# LM3S811_Module.net
KiCad netlist of a schematic drawn in EAGLE
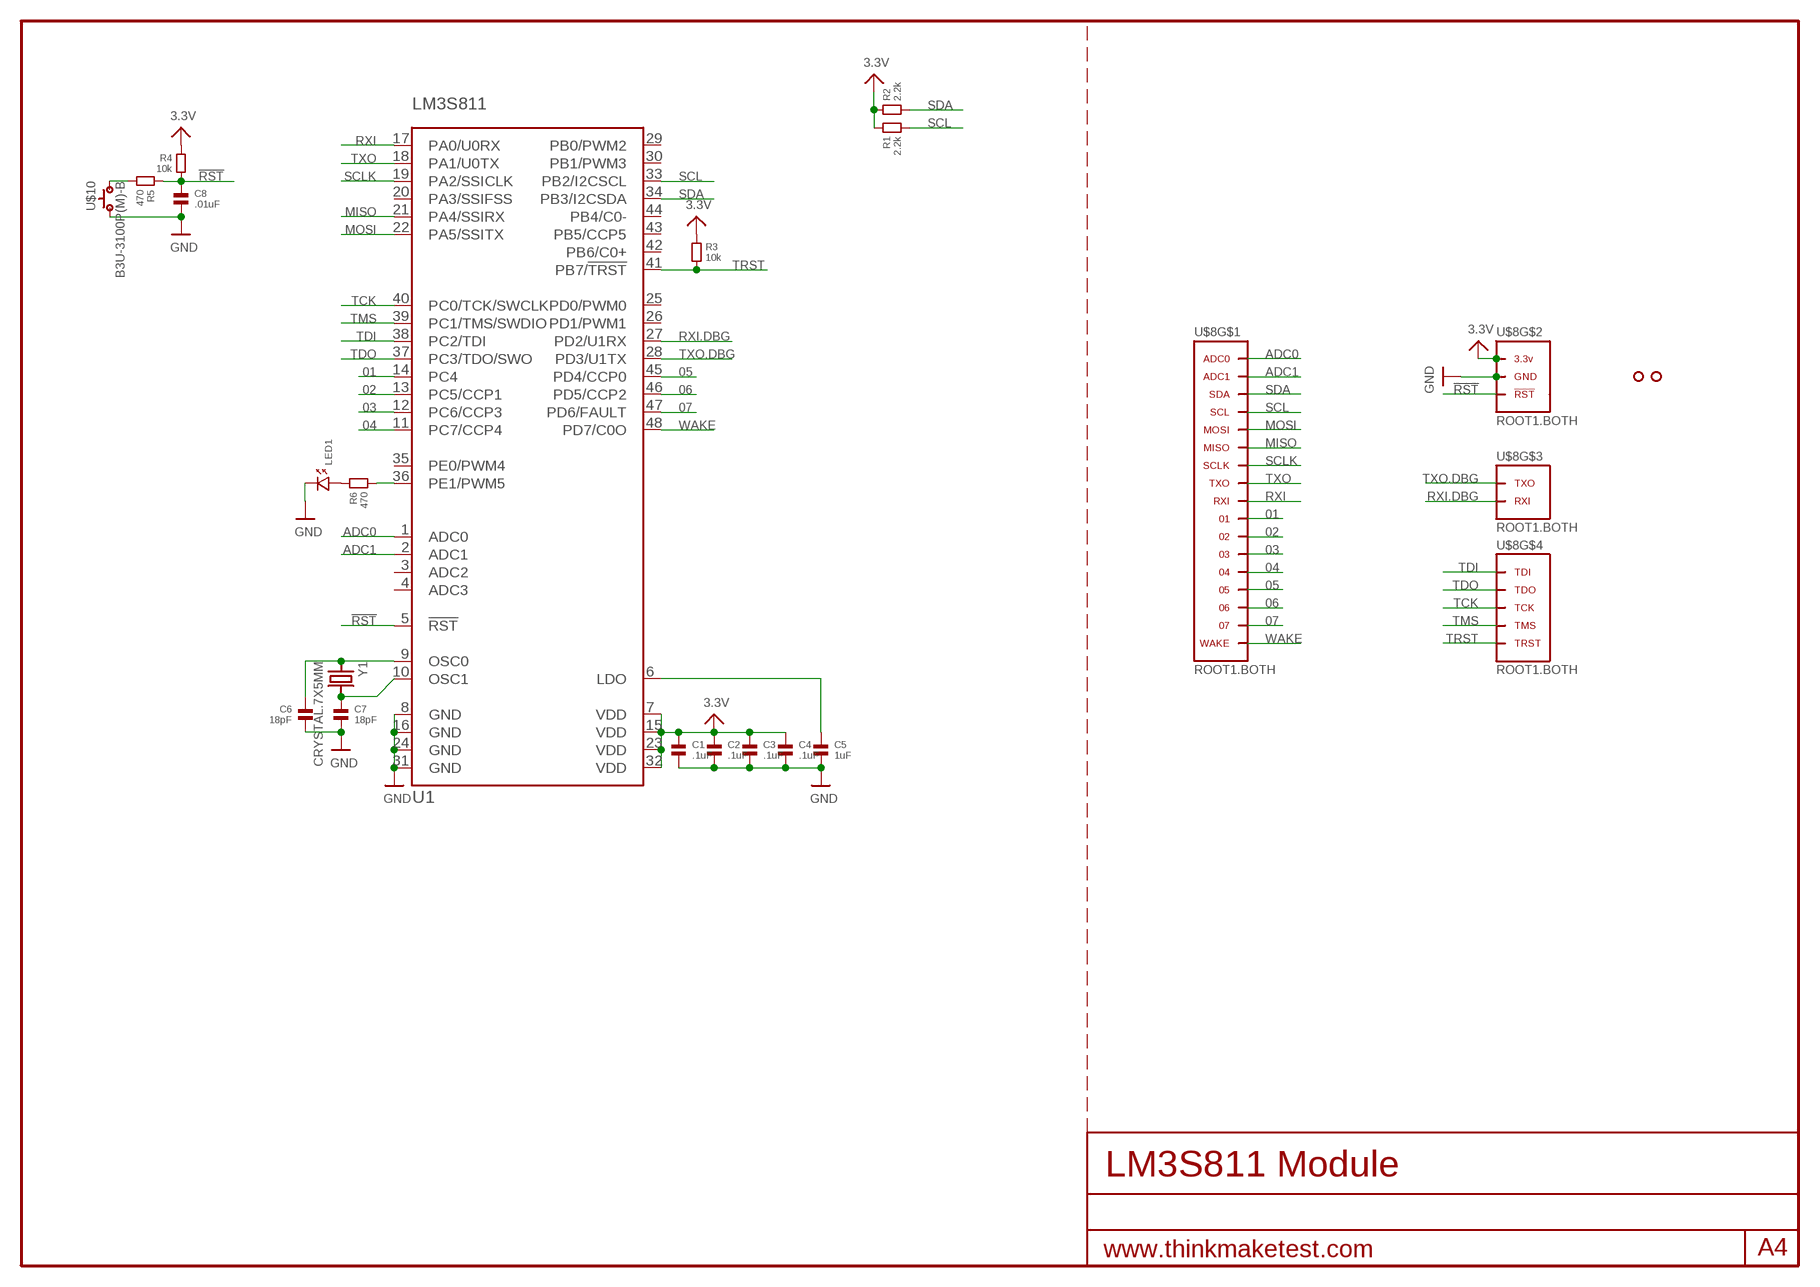
[diagram p0: schematic, sheet 1]

(export (version "E")
  (design (tool "Eeschema 10.0.6"))
  (components
    (comp (ref "C1")
      (value ".1uF")
      (footprint "eagle-import:0603")
      (libsource (lib "eagle-import") (part "CAPACITOR.0603"))
    )
    (comp (ref "C2")
      (value ".1uF")
      (footprint "eagle-import:0603")
      (libsource (lib "eagle-import") (part "CAPACITOR.0603"))
    )
    (comp (ref "C3")
      (value ".1uF")
      (footprint "eagle-import:0603")
      (libsource (lib "eagle-import") (part "CAPACITOR.0603"))
    )
    (comp (ref "C4")
      (value ".1uF")
      (footprint "eagle-import:0603")
      (libsource (lib "eagle-import") (part "CAPACITOR.0603"))
    )
    (comp (ref "C5")
      (value "1uF")
      (footprint "eagle-import:0603")
      (libsource (lib "eagle-import") (part "CAPACITOR.0603"))
    )
    (comp (ref "C6")
      (value "18pF")
      (footprint "eagle-import:0603")
      (libsource (lib "eagle-import") (part "CAPACITOR.0603"))
    )
    (comp (ref "C7")
      (value "18pF")
      (footprint "eagle-import:0603")
      (libsource (lib "eagle-import") (part "CAPACITOR.0603"))
    )
    (comp (ref "C8")
      (value ".01uF")
      (footprint "eagle-import:0603")
      (libsource (lib "eagle-import") (part "CAPACITOR.0603"))
    )
    (comp (ref "LED1")
      (value "LED.0603")
      (footprint "eagle-import:0603.LED")
      (libsource (lib "eagle-import") (part "LED.0603"))
    )
    (comp (ref "R1")
      (value "2.2k")
      (footprint "eagle-import:0603")
      (libsource (lib "eagle-import") (part "RESISTOR.0603"))
    )
    (comp (ref "R2")
      (value "2.2k")
      (footprint "eagle-import:0603")
      (libsource (lib "eagle-import") (part "RESISTOR.0603"))
    )
    (comp (ref "R3")
      (value "10k")
      (footprint "eagle-import:0603")
      (libsource (lib "eagle-import") (part "RESISTOR.0603"))
    )
    (comp (ref "R4")
      (value "10k")
      (footprint "eagle-import:0603")
      (libsource (lib "eagle-import") (part "RESISTOR.0603"))
    )
    (comp (ref "R5")
      (value "470")
      (footprint "eagle-import:0603")
      (libsource (lib "eagle-import") (part "RESISTOR.0603"))
    )
    (comp (ref "R6")
      (value "470")
      (footprint "eagle-import:0603")
      (libsource (lib "eagle-import") (part "RESISTOR.0603"))
    )
    (comp (ref "U$3")
      (value "HOLE.2MM")
      (footprint "eagle-import:2MM")
      (libsource (lib "eagle-import") (part "HOLE.2MM"))
    )
    (comp (ref "U$4")
      (value "HOLE.2MM")
      (footprint "eagle-import:2MM")
      (libsource (lib "eagle-import") (part "HOLE.2MM"))
    )
    (comp (ref "U$8")
      (value "ROOT1.BOTH")
      (footprint "eagle-import:ROOT1.BOTH")
      (libsource (lib "eagle-import") (part "ROOT1.BOTH"))
    )
    (comp (ref "U$10")
      (value "B3U-3100P(M)-B")
      (footprint "eagle-import:B3U-3100P(M)-B")
      (libsource (lib "eagle-import") (part "B3U-3100P(M)-B"))
    )
    (comp (ref "U1")
      (value "LM3S811")
      (footprint "eagle-import:QFP50P900X900X160-48N")
      (libsource (lib "eagle-import") (part "LM3S811"))
    )
    (comp (ref "Y1")
      (value "CRYSTAL.7X5MM")
      (footprint "eagle-import:7X5MM")
      (libsource (lib "eagle-import") (part "CRYSTAL.7X5MM"))
    )
  )
  (nets
    (net (code "1") (name "/01") (class "Default")
      (node (ref "U$8") (pin "01") (pinfunction "01_01") (pintype "bidirectional"))
      (node (ref "U$8") (pin "01@1") (pinfunction "01_01@1") (pintype "bidirectional"))
      (node (ref "U$8") (pin "01@VIA") (pinfunction "01_01@VIA") (pintype "bidirectional"))
      (node (ref "U1") (pin "14") (pinfunction "PC4_14") (pintype "bidirectional"))
    )
    (net (code "2") (name "/02") (class "Default")
      (node (ref "U$8") (pin "02") (pinfunction "02_02") (pintype "bidirectional"))
      (node (ref "U$8") (pin "02@1") (pinfunction "02_02@1") (pintype "bidirectional"))
      (node (ref "U$8") (pin "02@VIA") (pinfunction "02_02@VIA") (pintype "bidirectional"))
      (node (ref "U1") (pin "13") (pinfunction "PC5/CCP1_13") (pintype "bidirectional"))
    )
    (net (code "3") (name "/03") (class "Default")
      (node (ref "U$8") (pin "03") (pinfunction "03_03") (pintype "bidirectional"))
      (node (ref "U$8") (pin "03@1") (pinfunction "03_03@1") (pintype "bidirectional"))
      (node (ref "U$8") (pin "03@VIA") (pinfunction "03_03@VIA") (pintype "bidirectional"))
      (node (ref "U1") (pin "12") (pinfunction "PC6/CCP3_12") (pintype "bidirectional"))
    )
    (net (code "4") (name "/04") (class "Default")
      (node (ref "U$8") (pin "04") (pinfunction "04_04") (pintype "bidirectional"))
      (node (ref "U$8") (pin "04@1") (pinfunction "04_04@1") (pintype "bidirectional"))
      (node (ref "U$8") (pin "04@VIA") (pinfunction "04_04@VIA") (pintype "bidirectional"))
      (node (ref "U1") (pin "11") (pinfunction "PC7/CCP4_11") (pintype "bidirectional"))
    )
    (net (code "5") (name "/05") (class "Default")
      (node (ref "U$8") (pin "05") (pinfunction "05_05") (pintype "bidirectional"))
      (node (ref "U$8") (pin "05@1") (pinfunction "05_05@1") (pintype "bidirectional"))
      (node (ref "U$8") (pin "05@VIA") (pinfunction "05_05@VIA") (pintype "bidirectional"))
      (node (ref "U1") (pin "45") (pinfunction "PD4/CCP0_45") (pintype "bidirectional"))
    )
    (net (code "6") (name "/06") (class "Default")
      (node (ref "U$8") (pin "06") (pinfunction "06_06") (pintype "bidirectional"))
      (node (ref "U$8") (pin "06@1") (pinfunction "06_06@1") (pintype "bidirectional"))
      (node (ref "U$8") (pin "06@VIA") (pinfunction "06_06@VIA") (pintype "bidirectional"))
      (node (ref "U1") (pin "46") (pinfunction "PD5/CCP2_46") (pintype "bidirectional"))
    )
    (net (code "7") (name "/07") (class "Default")
      (node (ref "U$8") (pin "07") (pinfunction "07_07") (pintype "bidirectional"))
      (node (ref "U$8") (pin "07@1") (pinfunction "07_07@1") (pintype "bidirectional"))
      (node (ref "U$8") (pin "07@VIA") (pinfunction "07_07@VIA") (pintype "bidirectional"))
      (node (ref "U1") (pin "47") (pinfunction "PD6/FAULT_47") (pintype "bidirectional"))
    )
    (net (code "8") (name "/ADC0") (class "Default")
      (node (ref "U$8") (pin "ADC0") (pinfunction "ADC0_ADC0") (pintype "bidirectional"))
      (node (ref "U$8") (pin "ADC0@1") (pinfunction "ADC0_ADC0@1") (pintype "bidirectional"))
      (node (ref "U$8") (pin "ADC0@VIA") (pinfunction "ADC0_ADC0@VIA") (pintype "bidirectional"))
      (node (ref "U1") (pin "1") (pinfunction "ADC0_1") (pintype "bidirectional"))
    )
    (net (code "9") (name "/ADC1") (class "Default")
      (node (ref "U$8") (pin "ADC1") (pinfunction "ADC1_ADC1") (pintype "bidirectional"))
      (node (ref "U$8") (pin "ADC1@1") (pinfunction "ADC1_ADC1@1") (pintype "bidirectional"))
      (node (ref "U$8") (pin "ADC1@VIA") (pinfunction "ADC1_ADC1@VIA") (pintype "bidirectional"))
      (node (ref "U1") (pin "2") (pinfunction "ADC1_2") (pintype "bidirectional"))
    )
    (net (code "10") (name "/MISO") (class "Default")
      (node (ref "U$8") (pin "MISO") (pinfunction "MISO_MISO") (pintype "bidirectional"))
      (node (ref "U$8") (pin "MISO@1") (pinfunction "MISO_MISO@1") (pintype "bidirectional"))
      (node (ref "U$8") (pin "MISO@VIA") (pinfunction "MISO_MISO@VIA") (pintype "bidirectional"))
      (node (ref "U1") (pin "21") (pinfunction "PA4/SSIRX_21") (pintype "bidirectional"))
    )
    (net (code "11") (name "/MOSI") (class "Default")
      (node (ref "U$8") (pin "MOSI") (pinfunction "MOSI_MOSI") (pintype "bidirectional"))
      (node (ref "U$8") (pin "MOSI@1") (pinfunction "MOSI_MOSI@1") (pintype "bidirectional"))
      (node (ref "U$8") (pin "MOSI@VIA") (pinfunction "MOSI_MOSI@VIA") (pintype "bidirectional"))
      (node (ref "U1") (pin "22") (pinfunction "PA5/SSITX_22") (pintype "bidirectional"))
    )
    (net (code "12") (name "/RXI") (class "Default")
      (node (ref "U$8") (pin "RXI") (pinfunction "RXI_RXI") (pintype "bidirectional"))
      (node (ref "U$8") (pin "RXI@1") (pinfunction "RXI_RXI@1") (pintype "bidirectional"))
      (node (ref "U$8") (pin "RXI@VIA") (pinfunction "RXI_RXI@VIA") (pintype "bidirectional"))
      (node (ref "U1") (pin "17") (pinfunction "PA0/U0RX_17") (pintype "bidirectional"))
    )
    (net (code "13") (name "/RXI.DBG") (class "Default")
      (node (ref "U$8") (pin "RXI.DBG") (pinfunction "RXI_RXI.DBG") (pintype "bidirectional"))
      (node (ref "U$8") (pin "RXI.DBG@1") (pinfunction "RXI_RXI.DBG@1") (pintype "bidirectional"))
      (node (ref "U$8") (pin "RXI.DBG@VIA") (pinfunction "RXI_RXI.DBG@VIA") (pintype "bidirectional"))
      (node (ref "U1") (pin "27") (pinfunction "PD2/U1RX_27") (pintype "bidirectional"))
    )
    (net (code "14") (name "/SCL") (class "Default")
      (node (ref "R1") (pin "2") (pinfunction "2_2") (pintype "bidirectional"))
      (node (ref "U$8") (pin "SCL") (pinfunction "SCL_SCL") (pintype "bidirectional"))
      (node (ref "U$8") (pin "SCL@1") (pinfunction "SCL_SCL@1") (pintype "bidirectional"))
      (node (ref "U$8") (pin "SCL@VIA") (pinfunction "SCL_SCL@VIA") (pintype "bidirectional"))
      (node (ref "U1") (pin "33") (pinfunction "PB2/I2CSCL_33") (pintype "bidirectional"))
    )
    (net (code "15") (name "/SCLK") (class "Default")
      (node (ref "U$8") (pin "SCLK") (pinfunction "SCLK_SCLK") (pintype "bidirectional"))
      (node (ref "U$8") (pin "SCLK@1") (pinfunction "SCLK_SCLK@1") (pintype "bidirectional"))
      (node (ref "U$8") (pin "SCLK@VIA") (pinfunction "SCLK_SCLK@VIA") (pintype "bidirectional"))
      (node (ref "U1") (pin "19") (pinfunction "PA2/SSICLK_19") (pintype "bidirectional"))
    )
    (net (code "16") (name "/SDA") (class "Default")
      (node (ref "R2") (pin "2") (pinfunction "2_2") (pintype "bidirectional"))
      (node (ref "U$8") (pin "SDA") (pinfunction "SDA_SDA") (pintype "bidirectional"))
      (node (ref "U$8") (pin "SDA@1") (pinfunction "SDA_SDA@1") (pintype "bidirectional"))
      (node (ref "U$8") (pin "SDA@VIA") (pinfunction "SDA_SDA@VIA") (pintype "bidirectional"))
      (node (ref "U1") (pin "34") (pinfunction "PB3/I2CSDA_34") (pintype "bidirectional"))
    )
    (net (code "17") (name "/TCK") (class "Default")
      (node (ref "U$8") (pin "TCK") (pinfunction "TCK_TCK") (pintype "bidirectional"))
      (node (ref "U$8") (pin "TCK@1") (pinfunction "TCK_TCK@1") (pintype "bidirectional"))
      (node (ref "U$8") (pin "TCK@VIA") (pinfunction "TCK_TCK@VIA") (pintype "bidirectional"))
      (node (ref "U1") (pin "40") (pinfunction "PC0/TCK/SWCLK_40") (pintype "bidirectional"))
    )
    (net (code "18") (name "/TDI") (class "Default")
      (node (ref "U$8") (pin "TDI") (pinfunction "TDI_TDI") (pintype "bidirectional"))
      (node (ref "U$8") (pin "TDI@1") (pinfunction "TDI_TDI@1") (pintype "bidirectional"))
      (node (ref "U$8") (pin "TDI@VIA") (pinfunction "TDI_TDI@VIA") (pintype "bidirectional"))
      (node (ref "U1") (pin "38") (pinfunction "PC2/TDI_38") (pintype "bidirectional"))
    )
    (net (code "19") (name "/TDO") (class "Default")
      (node (ref "U$8") (pin "TDO") (pinfunction "TDO_TDO") (pintype "bidirectional"))
      (node (ref "U$8") (pin "TDO@1") (pinfunction "TDO_TDO@1") (pintype "bidirectional"))
      (node (ref "U$8") (pin "TDO@VIA") (pinfunction "TDO_TDO@VIA") (pintype "bidirectional"))
      (node (ref "U1") (pin "37") (pinfunction "PC3/TDO/SWO_37") (pintype "bidirectional"))
    )
    (net (code "20") (name "/TMS") (class "Default")
      (node (ref "U$8") (pin "TMS") (pinfunction "TMS_TMS") (pintype "bidirectional"))
      (node (ref "U$8") (pin "TMS@1") (pinfunction "TMS_TMS@1") (pintype "bidirectional"))
      (node (ref "U$8") (pin "TMS@VIA") (pinfunction "TMS_TMS@VIA") (pintype "bidirectional"))
      (node (ref "U1") (pin "39") (pinfunction "PC1/TMS/SWDIO_39") (pintype "bidirectional"))
    )
    (net (code "21") (name "/TRST") (class "Default")
      (node (ref "R3") (pin "2") (pinfunction "2_2") (pintype "bidirectional"))
      (node (ref "U$8") (pin "TRST") (pinfunction "TRST_TRST") (pintype "bidirectional"))
      (node (ref "U$8") (pin "TRST@1") (pinfunction "TRST_TRST@1") (pintype "bidirectional"))
      (node (ref "U$8") (pin "TRST@VIA") (pinfunction "TRST_TRST@VIA") (pintype "bidirectional"))
      (node (ref "U1") (pin "41") (pinfunction "PB7/~{TRST}_41") (pintype "bidirectional"))
    )
    (net (code "22") (name "/TXO") (class "Default")
      (node (ref "U$8") (pin "TXO") (pinfunction "TXO_TXO") (pintype "bidirectional"))
      (node (ref "U$8") (pin "TXO@1") (pinfunction "TXO_TXO@1") (pintype "bidirectional"))
      (node (ref "U$8") (pin "TXO@VIA") (pinfunction "TXO_TXO@VIA") (pintype "bidirectional"))
      (node (ref "U1") (pin "18") (pinfunction "PA1/U0TX_18") (pintype "bidirectional"))
    )
    (net (code "23") (name "/TXO.DBG") (class "Default")
      (node (ref "U$8") (pin "TXO.DBG") (pinfunction "TXO_TXO.DBG") (pintype "bidirectional"))
      (node (ref "U$8") (pin "TXO.DBG@1") (pinfunction "TXO_TXO.DBG@1") (pintype "bidirectional"))
      (node (ref "U$8") (pin "TXO.DBG@VIA") (pinfunction "TXO_TXO.DBG@VIA") (pintype "bidirectional"))
      (node (ref "U1") (pin "28") (pinfunction "PD3/U1TX_28") (pintype "bidirectional"))
    )
    (net (code "24") (name "/WAKE") (class "Default")
      (node (ref "U$8") (pin "WAKE") (pinfunction "WAKE_WAKE") (pintype "bidirectional"))
      (node (ref "U$8") (pin "WAKE@1") (pinfunction "WAKE_WAKE@1") (pintype "bidirectional"))
      (node (ref "U$8") (pin "WAKE@VIA") (pinfunction "WAKE_WAKE@VIA") (pintype "bidirectional"))
      (node (ref "U1") (pin "48") (pinfunction "PD7/C0O_48") (pintype "bidirectional"))
    )
    (net (code "25") (name "/~{RST}") (class "Default")
      (node (ref "C8") (pin "1") (pinfunction "1_1") (pintype "bidirectional"))
      (node (ref "R4") (pin "2") (pinfunction "2_2") (pintype "bidirectional"))
      (node (ref "R5") (pin "1") (pinfunction "1_1") (pintype "bidirectional"))
      (node (ref "U$8") (pin "RST") (pinfunction "~{RST}_RST") (pintype "bidirectional"))
      (node (ref "U$8") (pin "RST@1") (pinfunction "~{RST}_RST@1") (pintype "bidirectional"))
      (node (ref "U$8") (pin "RST@VIA") (pinfunction "~{RST}_RST@VIA") (pintype "bidirectional"))
      (node (ref "U1") (pin "5") (pinfunction "~{RST}_5") (pintype "bidirectional"))
    )
    (net (code "26") (name "3.3V") (class "Default")
      (node (ref "C1") (pin "1") (pinfunction "1_1") (pintype "bidirectional"))
      (node (ref "C2") (pin "1") (pinfunction "1_1") (pintype "bidirectional"))
      (node (ref "C3") (pin "1") (pinfunction "1_1") (pintype "bidirectional"))
      (node (ref "C4") (pin "1") (pinfunction "1_1") (pintype "bidirectional"))
      (node (ref "R1") (pin "1") (pinfunction "1_1") (pintype "bidirectional"))
      (node (ref "R2") (pin "1") (pinfunction "1_1") (pintype "bidirectional"))
      (node (ref "R3") (pin "1") (pinfunction "1_1") (pintype "bidirectional"))
      (node (ref "R4") (pin "1") (pinfunction "1_1") (pintype "bidirectional"))
      (node (ref "U$8") (pin "3.3V@1") (pinfunction "3.3V_3.3V@1") (pintype "bidirectional"))
      (node (ref "U$8") (pin "3.3V@10") (pinfunction "3.3V_3.3V@10") (pintype "bidirectional"))
      (node (ref "U$8") (pin "3.3V@11") (pinfunction "3.3V_3.3V@11") (pintype "bidirectional"))
      (node (ref "U$8") (pin "3.3V@12") (pinfunction "3.3V_3.3V@12") (pintype "bidirectional"))
      (node (ref "U$8") (pin "3.3V@13") (pinfunction "3.3V_3.3V@13") (pintype "bidirectional"))
      (node (ref "U$8") (pin "3.3V@14") (pinfunction "3.3V_3.3V@14") (pintype "bidirectional"))
      (node (ref "U$8") (pin "3.3V@15") (pinfunction "3.3V_3.3V@15") (pintype "bidirectional"))
      (node (ref "U$8") (pin "3.3V@16") (pinfunction "3.3V_3.3V@16") (pintype "bidirectional"))
      (node (ref "U$8") (pin "3.3V@17") (pinfunction "3.3V_3.3V@17") (pintype "bidirectional"))
      (node (ref "U$8") (pin "3.3V@18") (pinfunction "3.3V_3.3V@18") (pintype "bidirectional"))
      (node (ref "U$8") (pin "3.3V@19") (pinfunction "3.3V_3.3V@19") (pintype "bidirectional"))
      (node (ref "U$8") (pin "3.3V@2") (pinfunction "3.3V_3.3V@2") (pintype "bidirectional"))
      (node (ref "U$8") (pin "3.3V@20") (pinfunction "3.3V_3.3V@20") (pintype "bidirectional"))
      (node (ref "U$8") (pin "3.3V@21") (pinfunction "3.3V_3.3V@21") (pintype "bidirectional"))
      (node (ref "U$8") (pin "3.3V@22") (pinfunction "3.3V_3.3V@22") (pintype "bidirectional"))
      (node (ref "U$8") (pin "3.3V@23") (pinfunction "3.3V_3.3V@23") (pintype "bidirectional"))
      (node (ref "U$8") (pin "3.3V@24") (pinfunction "3.3V_3.3V@24") (pintype "bidirectional"))
      (node (ref "U$8") (pin "3.3V@3") (pinfunction "3.3V_3.3V@3") (pintype "bidirectional"))
      (node (ref "U$8") (pin "3.3V@4") (pinfunction "3.3V_3.3V@4") (pintype "bidirectional"))
      (node (ref "U$8") (pin "3.3V@5") (pinfunction "3.3V_3.3V@5") (pintype "bidirectional"))
      (node (ref "U$8") (pin "3.3V@6") (pinfunction "3.3V_3.3V@6") (pintype "bidirectional"))
      (node (ref "U$8") (pin "3.3V@7") (pinfunction "3.3V_3.3V@7") (pintype "bidirectional"))
      (node (ref "U$8") (pin "3.3V@8") (pinfunction "3.3V_3.3V@8") (pintype "bidirectional"))
      (node (ref "U$8") (pin "3.3V@9") (pinfunction "3.3V_3.3V@9") (pintype "bidirectional"))
      (node (ref "U$8") (pin "3.3V@VIA") (pinfunction "3.3V_3.3V@VIA") (pintype "bidirectional"))
      (node (ref "U1") (pin "15") (pinfunction "VDD_15") (pintype "bidirectional"))
      (node (ref "U1") (pin "23") (pinfunction "VDD_23") (pintype "bidirectional"))
      (node (ref "U1") (pin "32") (pinfunction "VDD_32") (pintype "bidirectional"))
      (node (ref "U1") (pin "7") (pinfunction "VDD_7") (pintype "bidirectional"))
    )
    (net (code "27") (name "GND") (class "Default")
      (node (ref "C1") (pin "2") (pinfunction "2_2") (pintype "bidirectional"))
      (node (ref "C2") (pin "2") (pinfunction "2_2") (pintype "bidirectional"))
      (node (ref "C3") (pin "2") (pinfunction "2_2") (pintype "bidirectional"))
      (node (ref "C4") (pin "2") (pinfunction "2_2") (pintype "bidirectional"))
      (node (ref "C5") (pin "2") (pinfunction "2_2") (pintype "bidirectional"))
      (node (ref "C6") (pin "2") (pinfunction "2_2") (pintype "bidirectional"))
      (node (ref "C7") (pin "2") (pinfunction "2_2") (pintype "bidirectional"))
      (node (ref "C8") (pin "2") (pinfunction "2_2") (pintype "bidirectional"))
      (node (ref "LED1") (pin "P$2") (pinfunction "2_P$2") (pintype "bidirectional"))
      (node (ref "U$10") (pin "2") (pinfunction "2_2") (pintype "bidirectional"))
      (node (ref "U$8") (pin "GND@1") (pinfunction "GND_GND@1") (pintype "bidirectional"))
      (node (ref "U$8") (pin "GND@10") (pinfunction "GND_GND@10") (pintype "bidirectional"))
      (node (ref "U$8") (pin "GND@11") (pinfunction "GND_GND@11") (pintype "bidirectional"))
      (node (ref "U$8") (pin "GND@12") (pinfunction "GND_GND@12") (pintype "bidirectional"))
      (node (ref "U$8") (pin "GND@13") (pinfunction "GND_GND@13") (pintype "bidirectional"))
      (node (ref "U$8") (pin "GND@14") (pinfunction "GND_GND@14") (pintype "bidirectional"))
      (node (ref "U$8") (pin "GND@15") (pinfunction "GND_GND@15") (pintype "bidirectional"))
      (node (ref "U$8") (pin "GND@16") (pinfunction "GND_GND@16") (pintype "bidirectional"))
      (node (ref "U$8") (pin "GND@17") (pinfunction "GND_GND@17") (pintype "bidirectional"))
      (node (ref "U$8") (pin "GND@18") (pinfunction "GND_GND@18") (pintype "bidirectional"))
      (node (ref "U$8") (pin "GND@19") (pinfunction "GND_GND@19") (pintype "bidirectional"))
      (node (ref "U$8") (pin "GND@2") (pinfunction "GND_GND@2") (pintype "bidirectional"))
      (node (ref "U$8") (pin "GND@20") (pinfunction "GND_GND@20") (pintype "bidirectional"))
      (node (ref "U$8") (pin "GND@21") (pinfunction "GND_GND@21") (pintype "bidirectional"))
      (node (ref "U$8") (pin "GND@22") (pinfunction "GND_GND@22") (pintype "bidirectional"))
      (node (ref "U$8") (pin "GND@23") (pinfunction "GND_GND@23") (pintype "bidirectional"))
      (node (ref "U$8") (pin "GND@24") (pinfunction "GND_GND@24") (pintype "bidirectional"))
      (node (ref "U$8") (pin "GND@25") (pinfunction "GND_GND@25") (pintype "bidirectional"))
      (node (ref "U$8") (pin "GND@26") (pinfunction "GND_GND@26") (pintype "bidirectional"))
      (node (ref "U$8") (pin "GND@3") (pinfunction "GND_GND@3") (pintype "bidirectional"))
      (node (ref "U$8") (pin "GND@4") (pinfunction "GND_GND@4") (pintype "bidirectional"))
      (node (ref "U$8") (pin "GND@5") (pinfunction "GND_GND@5") (pintype "bidirectional"))
      (node (ref "U$8") (pin "GND@6") (pinfunction "GND_GND@6") (pintype "bidirectional"))
      (node (ref "U$8") (pin "GND@7") (pinfunction "GND_GND@7") (pintype "bidirectional"))
      (node (ref "U$8") (pin "GND@8") (pinfunction "GND_GND@8") (pintype "bidirectional"))
      (node (ref "U$8") (pin "GND@9") (pinfunction "GND_GND@9") (pintype "bidirectional"))
      (node (ref "U$8") (pin "GND@VIA") (pinfunction "GND_GND@VIA") (pintype "bidirectional"))
      (node (ref "U1") (pin "16") (pinfunction "GND_16") (pintype "bidirectional"))
      (node (ref "U1") (pin "24") (pinfunction "GND_24") (pintype "bidirectional"))
      (node (ref "U1") (pin "31") (pinfunction "GND_31") (pintype "bidirectional"))
      (node (ref "U1") (pin "8") (pinfunction "GND_8") (pintype "bidirectional"))
    )
    (net (code "28") (name "Net-(LED1-1)") (class "Default")
      (node (ref "LED1") (pin "P$1") (pinfunction "1_P$1") (pintype "bidirectional"))
      (node (ref "R6") (pin "1") (pinfunction "1_1") (pintype "bidirectional"))
    )
    (net (code "29") (name "Net-(R5-Pad2)") (class "Default")
      (node (ref "R5") (pin "2") (pinfunction "2_2") (pintype "bidirectional"))
      (node (ref "U$10") (pin "1") (pinfunction "1_1") (pintype "bidirectional"))
    )
    (net (code "30") (name "Net-(U1-LDO)") (class "Default")
      (node (ref "C5") (pin "1") (pinfunction "1_1") (pintype "bidirectional"))
      (node (ref "U1") (pin "6") (pinfunction "LDO_6") (pintype "bidirectional"))
    )
    (net (code "31") (name "Net-(U1-OSC0)") (class "Default")
      (node (ref "C6") (pin "1") (pinfunction "1_1") (pintype "bidirectional"))
      (node (ref "U1") (pin "9") (pinfunction "OSC0_9") (pintype "bidirectional"))
      (node (ref "Y1") (pin "1") (pinfunction "1_1") (pintype "passive"))
    )
    (net (code "32") (name "Net-(U1-OSC1)") (class "Default")
      (node (ref "C7") (pin "1") (pinfunction "1_1") (pintype "bidirectional"))
      (node (ref "U1") (pin "10") (pinfunction "OSC1_10") (pintype "bidirectional"))
      (node (ref "Y1") (pin "3") (pinfunction "2_3") (pintype "passive"))
    )
    (net (code "33") (name "Net-(U1-PE1{slash}PWM5)") (class "Default")
      (node (ref "R6") (pin "2") (pinfunction "2_2") (pintype "bidirectional"))
      (node (ref "U1") (pin "36") (pinfunction "PE1/PWM5_36") (pintype "bidirectional"))
    )
    (net (code "34") (name "unconnected-(U1-ADC2-Pad3)") (class "Default")
      (node (ref "U1") (pin "3") (pinfunction "ADC2_3") (pintype "bidirectional"))
    )
    (net (code "35") (name "unconnected-(U1-ADC3-Pad4)") (class "Default")
      (node (ref "U1") (pin "4") (pinfunction "ADC3_4") (pintype "bidirectional"))
    )
    (net (code "36") (name "unconnected-(U1-PA3{slash}SSIFSS-Pad20)") (class "Default")
      (node (ref "U1") (pin "20") (pinfunction "PA3/SSIFSS_20") (pintype "bidirectional"))
    )
    (net (code "37") (name "unconnected-(U1-PB0{slash}PWM2-Pad29)") (class "Default")
      (node (ref "U1") (pin "29") (pinfunction "PB0/PWM2_29") (pintype "bidirectional"))
    )
    (net (code "38") (name "unconnected-(U1-PB1{slash}PWM3-Pad30)") (class "Default")
      (node (ref "U1") (pin "30") (pinfunction "PB1/PWM3_30") (pintype "bidirectional"))
    )
    (net (code "39") (name "unconnected-(U1-PB4{slash}C0--Pad44)") (class "Default")
      (node (ref "U1") (pin "44") (pinfunction "PB4/C0-_44") (pintype "bidirectional"))
    )
    (net (code "40") (name "unconnected-(U1-PB5{slash}CCP5-Pad43)") (class "Default")
      (node (ref "U1") (pin "43") (pinfunction "PB5/CCP5_43") (pintype "bidirectional"))
    )
    (net (code "41") (name "unconnected-(U1-PB6{slash}C0+-Pad42)") (class "Default")
      (node (ref "U1") (pin "42") (pinfunction "PB6/C0+_42") (pintype "bidirectional"))
    )
    (net (code "42") (name "unconnected-(U1-PD0{slash}PWM0-Pad25)") (class "Default")
      (node (ref "U1") (pin "25") (pinfunction "PD0/PWM0_25") (pintype "bidirectional"))
    )
    (net (code "43") (name "unconnected-(U1-PD1{slash}PWM1-Pad26)") (class "Default")
      (node (ref "U1") (pin "26") (pinfunction "PD1/PWM1_26") (pintype "bidirectional"))
    )
    (net (code "44") (name "unconnected-(U1-PE0{slash}PWM4-Pad35)") (class "Default")
      (node (ref "U1") (pin "35") (pinfunction "PE0/PWM4_35") (pintype "bidirectional"))
    )
  )
)
